# Bomba_Aire.net
KiCad netlist of a schematic drawn in Altium Designer
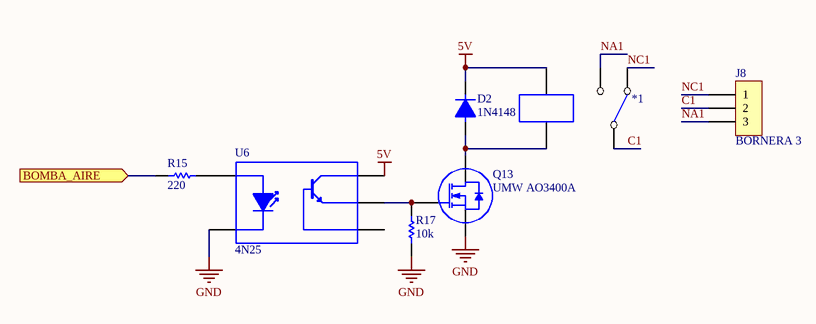
[diagram p0: Bomba Aire.SchDoc]

(export (version "E")
  (design (tool "Eeschema 10.0.6"))
  (components
    (comp (ref "*1")
      (value "RELE SIMPLE")
      (footprint "RELE SERIE 964")
      (libsource (lib "LIBPIOIX") (part "RELE SIMPLE"))
    )
    (comp (ref "D2") (value "1N4148") (footprint "1206K") (libsource (lib "LIBPIOIX") (part "DIODO")))
    (comp (ref "J8")
      (value "BORNERA 3")
      (footprint "BORNERA3")
      (libsource (lib "LIBPIOIX") (part "BORNERA 3"))
    )
    (comp (ref "Q13")
      (value "UMW AO3400A")
      (footprint "SOT23")
      (libsource (lib "LIBPIOIX") (part "MOSFET N"))
    )
    (comp (ref "R15") (value "220") (footprint "0805") (libsource (lib "LIBPIOIX") (part "RES")))
    (comp (ref "R17") (value "10k") (footprint "0805") (libsource (lib "LIBPIOIX") (part "RES")))
    (comp (ref "U6") (value "4N25") (footprint "SMD6") (libsource (lib "LIBPIOIX") (part "4N25")))
  )
  (nets
    (net (code "1") (name "/BOMBA_AIRE") (class "Default")
      (node (ref "R15") (pin "1") (pinfunction "1_1") (pintype "passive"))
    )
    (net (code "2") (name "/C1") (class "Default")
      (node (ref "*1") (pin "C1") (pinfunction "C1_C1") (pintype "passive"))
      (node (ref "J8") (pin "2") (pinfunction "2_2") (pintype "passive"))
    )
    (net (code "3") (name "/NA1") (class "Default")
      (node (ref "*1") (pin "NA1") (pinfunction "NA1_NA1") (pintype "passive"))
      (node (ref "J8") (pin "3") (pinfunction "3_3") (pintype "passive"))
    )
    (net (code "4") (name "/NC1") (class "Default")
      (node (ref "*1") (pin "NC1") (pinfunction "NC1_NC1") (pintype "passive"))
      (node (ref "J8") (pin "1") (pinfunction "1_1") (pintype "passive"))
    )
    (net (code "5") (name "5V") (class "Default")
      (node (ref "*1") (pin "B1") (pinfunction "B1_B1") (pintype "passive"))
      (node (ref "D2") (pin "2") (pinfunction "2_2") (pintype "passive"))
      (node (ref "U6") (pin "5") (pinfunction "C_5") (pintype "passive"))
    )
    (net (code "6") (name "GND") (class "Default")
      (node (ref "Q13") (pin "3") (pinfunction "S_3") (pintype "passive"))
      (node (ref "R17") (pin "1") (pinfunction "1_1") (pintype "passive"))
      (node (ref "U6") (pin "2") (pinfunction "K_2") (pintype "passive"))
    )
    (net (code "7") (name "Net-(Q13-D)") (class "Default")
      (node (ref "*1") (pin "B2") (pinfunction "B2_B2") (pintype "passive"))
      (node (ref "D2") (pin "1") (pinfunction "1_1") (pintype "passive"))
      (node (ref "Q13") (pin "2") (pinfunction "D_2") (pintype "passive"))
    )
    (net (code "8") (name "Net-(Q13-G)") (class "Default")
      (node (ref "Q13") (pin "1") (pinfunction "G_1") (pintype "passive"))
      (node (ref "R17") (pin "2") (pinfunction "2_2") (pintype "passive"))
      (node (ref "U6") (pin "4") (pinfunction "E_4") (pintype "passive"))
    )
    (net (code "9") (name "Net-(U6-A)") (class "Default")
      (node (ref "R15") (pin "2") (pinfunction "2_2") (pintype "passive"))
      (node (ref "U6") (pin "1") (pinfunction "A_1") (pintype "passive"))
    )
    (net (code "10") (name "unconnected-(U6-B-Pad6)") (class "Default")
      (node (ref "U6") (pin "6") (pinfunction "B_6") (pintype "passive"))
    )
  )
)
